# SCH_Aquacontrol_2026-05-27.net
KiCad netlist of a schematic drawn in EasyEDA
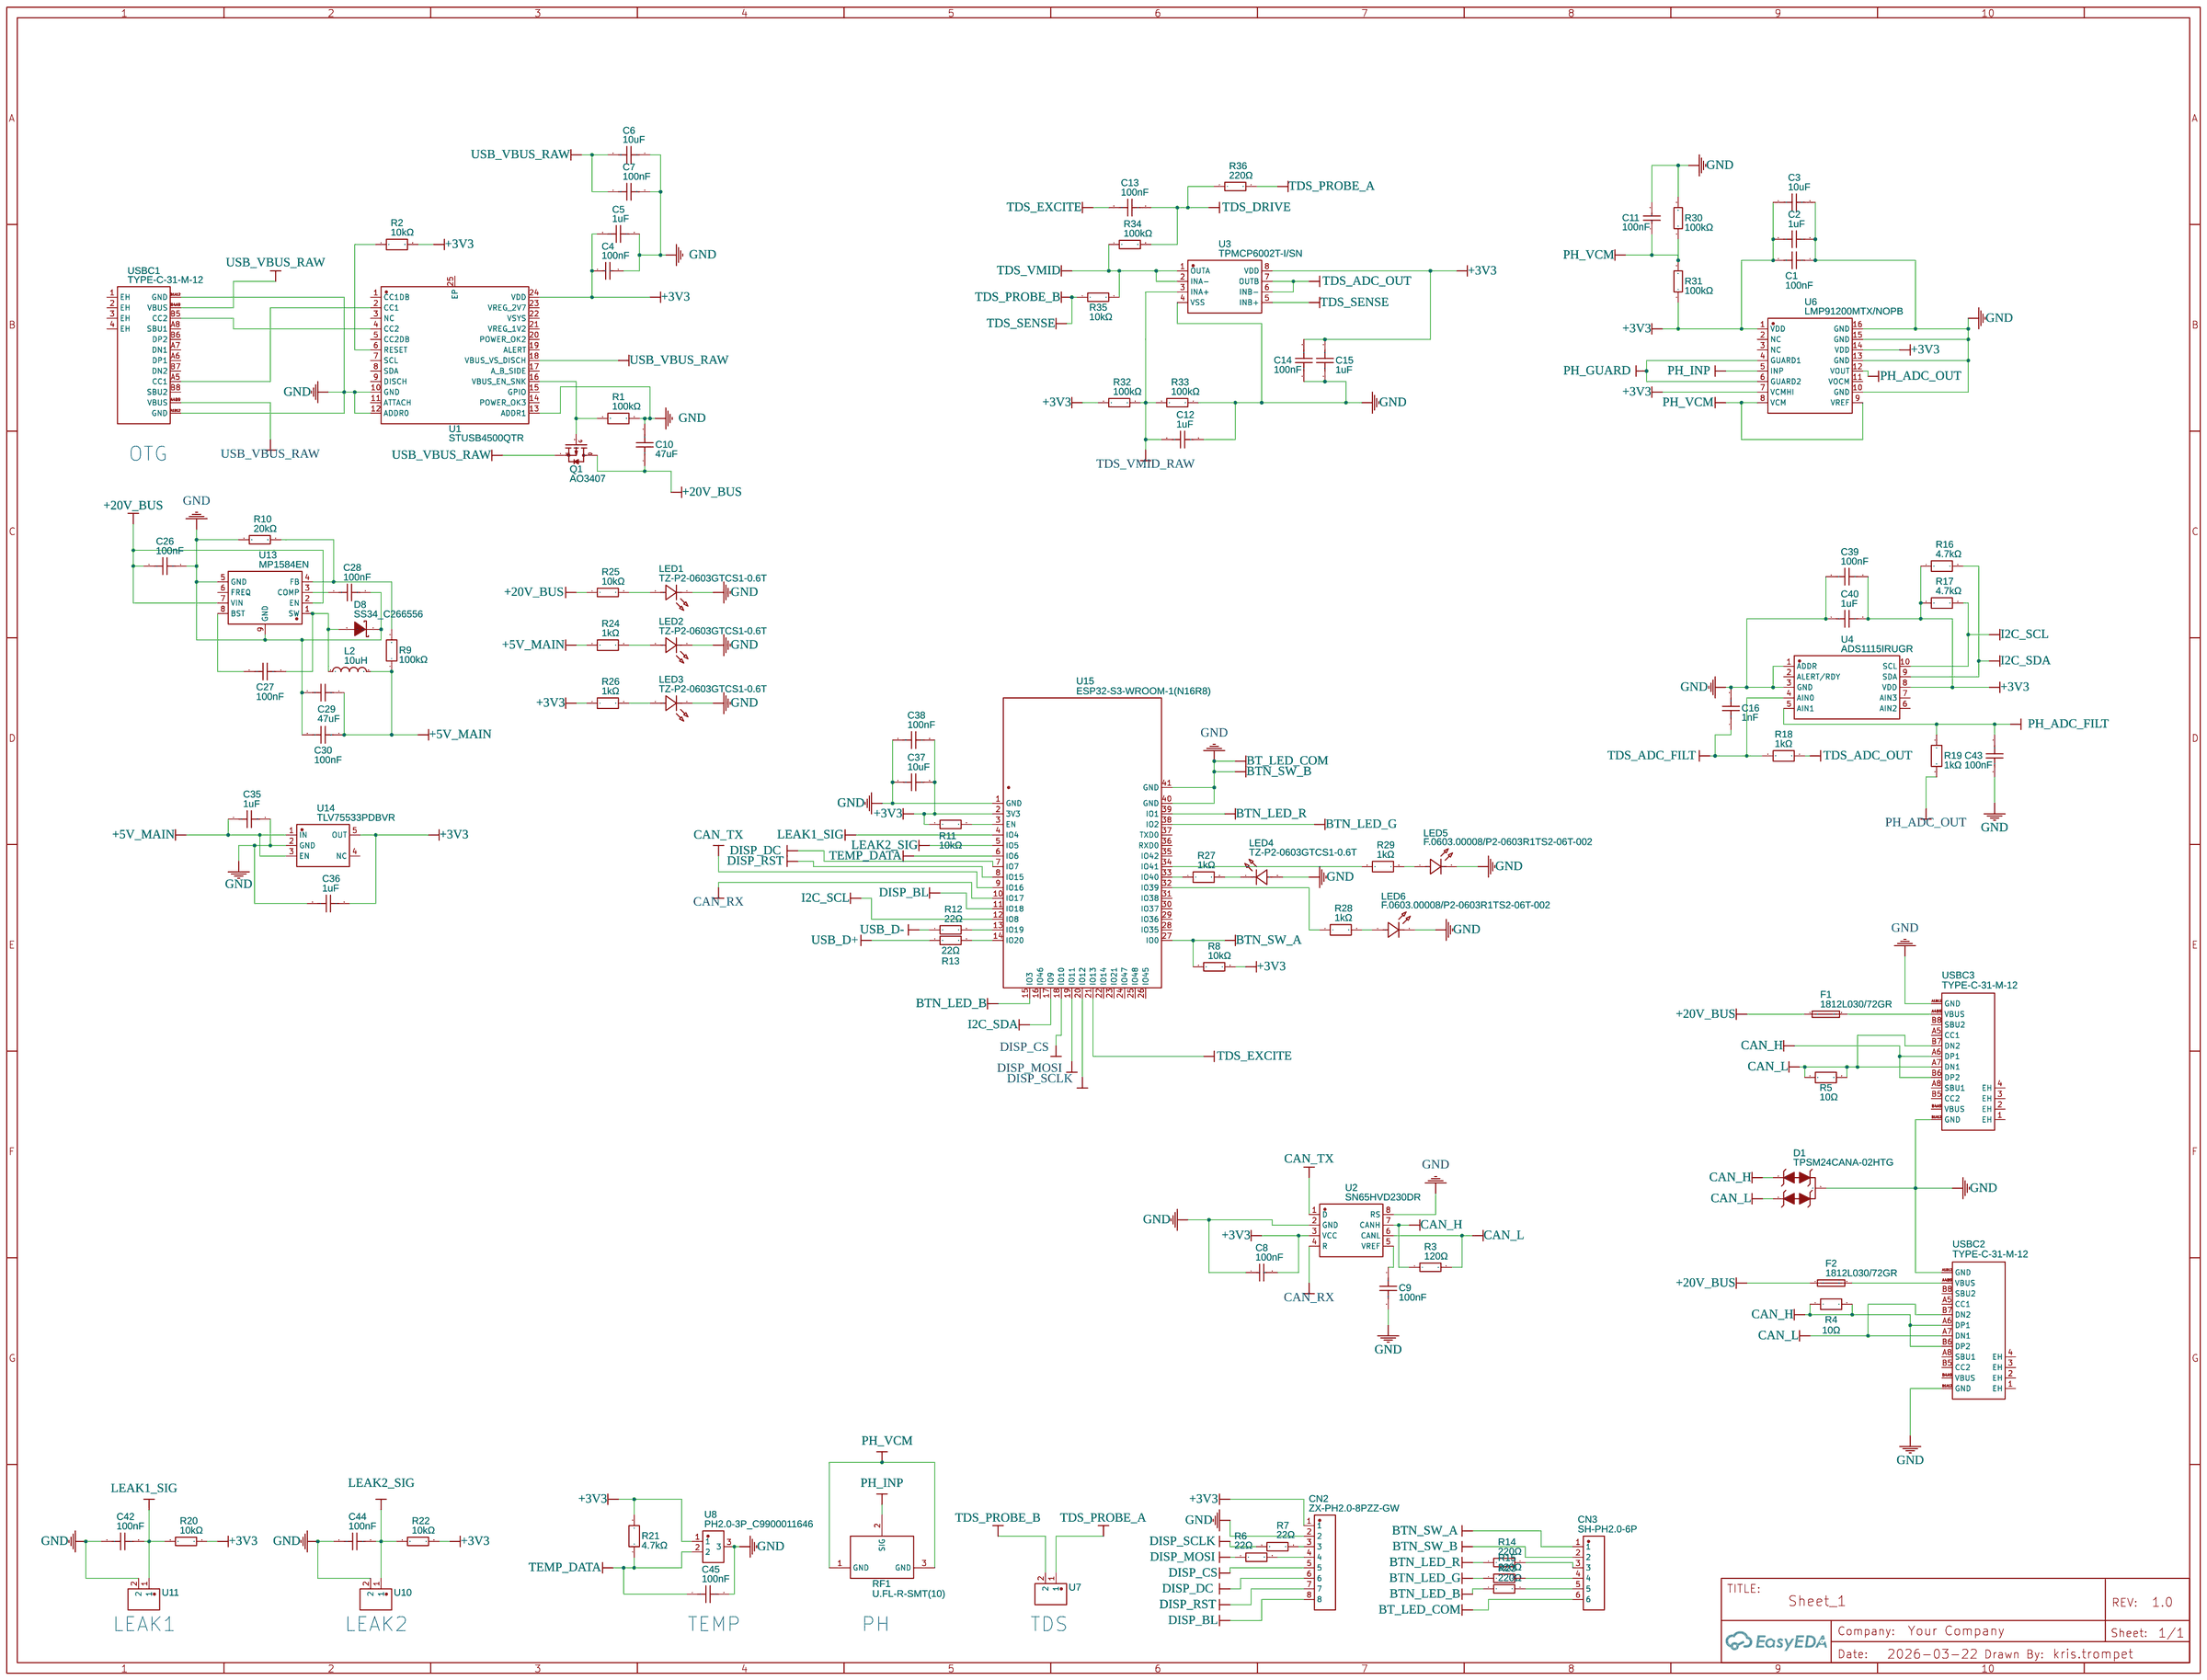
[diagram p0: schematic sheet]

(export (version "E")
  (design (tool "Eeschema 10.0.6"))
  (components
    (comp (ref "C1")
      (value "100nF")
      (fields (field (name "Manufacturer Part") "0603B104J250NT") (field (name "Manufacturer") "FH(风华)"))
      (libsource (lib "") (part "0603B104J250NT"))
    )
    (comp (ref "C2")
      (value "1uF")
      (fields
        (field (name "Manufacturer Part") "TCC0603X5R105M250CT")
        (field (name "Manufacturer") "CCTC(三环)")
      )
      (libsource (lib "") (part "TCC0603X5R105M250CT"))
    )
    (comp (ref "C3")
      (value "10uF")
      (fields
        (field (name "Manufacturer Part") "0805X5R106M500NT")
        (field (name "Manufacturer") "AIDE(爱迪电容)")
      )
      (libsource (lib "") (part "0805X5R106M500NT"))
    )
    (comp (ref "C4")
      (value "100nF")
      (fields (field (name "Manufacturer Part") "06035C104KAT2A") (field (name "Manufacturer") "Kyocera AVX"))
      (libsource (lib "") (part "06035C104KAT2A"))
    )
    (comp (ref "C5")
      (value "1uF")
      (fields (field (name "Manufacturer Part") "0603B105J160CT") (field (name "Manufacturer") "Walsin(华新科)"))
      (libsource (lib "") (part "0603B105J160CT"))
    )
    (comp (ref "C6")
      (value "10uF")
      (fields (field (name "Manufacturer Part") "1206B106K100NT") (field (name "Manufacturer") "FH(风华)"))
      (libsource (lib "") (part "1206B106K100NT"))
    )
    (comp (ref "C7")
      (value "100nF")
      (fields (field (name "Manufacturer Part") "0603B104J500NT") (field (name "Manufacturer") "FH(风华)"))
      (libsource (lib "") (part "0603B104J500NT"))
    )
    (comp (ref "C8")
      (value "100nF")
      (fields (field (name "Manufacturer Part") "06035C104KAT2A") (field (name "Manufacturer") "Kyocera AVX"))
      (libsource (lib "") (part "06035C104KAT2A"))
    )
    (comp (ref "C9")
      (value "100nF")
      (fields
        (field (name "Manufacturer Part") "0603X7R104K100NT")
        (field (name "Manufacturer") "AIDE(爱迪电容)")
      )
      (libsource (lib "") (part "0603X7R104K100NT_1"))
    )
    (comp (ref "C10")
      (value "47uF")
      (fields
        (field (name "Manufacturer Part") "TCC1206X5R476M100HT")
        (field (name "Manufacturer") "CCTC(三环)")
      )
      (libsource (lib "") (part "TCC1206X5R476M100HT"))
    )
    (comp (ref "C11")
      (value "100nF")
      (fields
        (field (name "Manufacturer Part") "CT41G-0603-2X1-50V-0.1uF-K(N)")
        (field (name "Manufacturer") "TORCH(火炬)")
      )
      (libsource (lib "") (part "CT41G-0603-2X1-50V-0.1μF-K(N)"))
    )
    (comp (ref "C12")
      (value "1uF")
      (fields
        (field (name "Manufacturer Part") "TCC0603X5R105M250CT")
        (field (name "Manufacturer") "CCTC(三环)")
      )
      (libsource (lib "") (part "TCC0603X5R105M250CT"))
    )
    (comp (ref "C13")
      (value "100nF")
      (fields
        (field (name "Manufacturer Part") "0603X7R104K100NT")
        (field (name "Manufacturer") "AIDE(爱迪电容)")
      )
      (libsource (lib "") (part "0603X7R104K100NT_3"))
    )
    (comp (ref "C14")
      (value "100nF")
      (fields
        (field (name "Manufacturer Part") "0603X7R104K100NT")
        (field (name "Manufacturer") "AIDE(爱迪电容)")
      )
      (libsource (lib "") (part "0603X7R104K100NT"))
    )
    (comp (ref "C15")
      (value "1uF")
      (fields
        (field (name "Manufacturer Part") "TCC0603X5R105M250CT")
        (field (name "Manufacturer") "CCTC(三环)")
      )
      (libsource (lib "") (part "TCC0603X5R105M250CT_1"))
    )
    (comp (ref "C16")
      (value "1nF")
      (fields
        (field (name "Manufacturer Part") "AC0603KRX7R9BB102")
        (field (name "Manufacturer") "YAGEO(国巨)")
      )
      (libsource (lib "") (part "AC0603KRX7R9BB102"))
    )
    (comp (ref "C26")
      (value "100nF")
      (fields (field (name "Manufacturer Part") "0603B104J250NT") (field (name "Manufacturer") "FH(风华)"))
      (libsource (lib "") (part "0603B104J250NT"))
    )
    (comp (ref "C27")
      (value "100nF")
      (fields (field (name "Manufacturer Part") "0603B104J250NT") (field (name "Manufacturer") "FH(风华)"))
      (libsource (lib "") (part "0603B104J250NT"))
    )
    (comp (ref "C28")
      (value "100nF")
      (fields (field (name "Manufacturer Part") "0603B104J250NT") (field (name "Manufacturer") "FH(风华)"))
      (libsource (lib "") (part "0603B104J250NT_1"))
    )
    (comp (ref "C29")
      (value "47uF")
      (fields
        (field (name "Manufacturer Part") "CGA0603X5R476M6R3JT")
        (field (name "Manufacturer") "HRE(芯声)")
      )
      (libsource (lib "") (part "CGA0603X5R476M6R3JT"))
    )
    (comp (ref "C30")
      (value "100nF")
      (fields (field (name "Manufacturer Part") "0603B104J250NT") (field (name "Manufacturer") "FH(风华)"))
      (libsource (lib "") (part "0603B104J250NT"))
    )
    (comp (ref "C35")
      (value "1uF")
      (fields
        (field (name "Manufacturer Part") "CSA0603X5R105K160JT")
        (field (name "Manufacturer") "HRE(芯声)")
      )
      (libsource (lib "") (part "CSA0603X5R105K160JT"))
    )
    (comp (ref "C36")
      (value "1uF")
      (fields
        (field (name "Manufacturer Part") "CSA0603X5R105K160JT")
        (field (name "Manufacturer") "HRE(芯声)")
      )
      (libsource (lib "") (part "CSA0603X5R105K160JT"))
    )
    (comp (ref "C37")
      (value "10uF")
      (fields
        (field (name "Manufacturer Part") "CGA0805X7R106K100MT")
        (field (name "Manufacturer") "HRE(芯声)")
      )
      (libsource (lib "") (part "CGA0805X7R106K100MT"))
    )
    (comp (ref "C38")
      (value "100nF")
      (fields
        (field (name "Manufacturer Part") "0603X7R104K100NT")
        (field (name "Manufacturer") "AIDE(爱迪电容)")
      )
      (libsource (lib "") (part "0603X7R104K100NT_2"))
    )
    (comp (ref "C39")
      (value "100nF")
      (fields
        (field (name "Manufacturer Part") "0603X7R104K100NT")
        (field (name "Manufacturer") "AIDE(爱迪电容)")
      )
      (libsource (lib "") (part "0603X7R104K100NT_2"))
    )
    (comp (ref "C40")
      (value "1uF")
      (fields
        (field (name "Manufacturer Part") "TCC0603X5R105M250CT")
        (field (name "Manufacturer") "CCTC(三环)")
      )
      (libsource (lib "") (part "TCC0603X5R105M250CT"))
    )
    (comp (ref "C42")
      (value "100nF")
      (fields
        (field (name "Manufacturer Part") "0603X7R104K100NT")
        (field (name "Manufacturer") "AIDE(爱迪电容)")
      )
      (libsource (lib "") (part "0603X7R104K100NT_2"))
    )
    (comp (ref "C43")
      (value "100nF")
      (fields
        (field (name "Manufacturer Part") "0603X7R104K100NT")
        (field (name "Manufacturer") "AIDE(爱迪电容)")
      )
      (libsource (lib "") (part "0603X7R104K100NT"))
    )
    (comp (ref "C44")
      (value "100nF")
      (fields
        (field (name "Manufacturer Part") "0603X7R104K100NT")
        (field (name "Manufacturer") "AIDE(爱迪电容)")
      )
      (libsource (lib "") (part "0603X7R104K100NT_2"))
    )
    (comp (ref "C45")
      (value "100nF")
      (fields
        (field (name "Manufacturer Part") "0603X7R104K100NT")
        (field (name "Manufacturer") "AIDE(爱迪电容)")
      )
      (libsource (lib "") (part "0603X7R104K100NT_2"))
    )
    (comp (ref "CN2")
      (value "ZX-PH2.0-8PZZ-GW")
      (fields (field (name "Manufacturer") "Megastar(兆星)"))
      (libsource (lib "") (part "ZX-PH2.0-8PZZ-GW"))
    )
    (comp (ref "CN3")
      (value "SH-PH2.0-6P")
      (fields (field (name "Manufacturer") "深海电子"))
      (libsource (lib "") (part "SH-PH2.0-6P"))
    )
    (comp (ref "D1")
      (value "TPSM24CANA-02HTG")
      (fields (field (name "Manufacturer") "TECH PUBLIC(台舟)"))
      (libsource (lib "") (part "TPSM24CANA-02HTG"))
    )
    (comp (ref "D8")
      (value "SS34_C266556")
      (fields (field (name "Manufacturer Part") "SS34") (field (name "Manufacturer") "BORN(伯恩半导体)"))
      (libsource (lib "") (part "SS34_C266556"))
    )
    (comp (ref "F1")
      (value "1812L030/72GR")
      (fields (field (name "Manufacturer") "LUTE(陆特)"))
      (libsource (lib "") (part "1812L030/72GR"))
    )
    (comp (ref "F2")
      (value "1812L030/72GR")
      (fields (field (name "Manufacturer") "LUTE(陆特)"))
      (libsource (lib "") (part "1812L030/72GR"))
    )
    (comp (ref "L2")
      (value "10uH")
      (fields (field (name "Manufacturer Part") "SMDRI129-100MT") (field (name "Manufacturer") "SXN(顺翔诺)"))
      (libsource (lib "") (part "SMDRI129-100MT"))
    )
    (comp (ref "LED1")
      (value "TZ-P2-0603GTCS1-0.6T")
      (fields (field (name "Manufacturer") "TUOZHAN(拓展光电)"))
      (libsource (lib "") (part "TZ-P2-0603GTCS1-0.6T_1"))
    )
    (comp (ref "LED2")
      (value "TZ-P2-0603GTCS1-0.6T")
      (fields (field (name "Manufacturer") "TUOZHAN(拓展光电)"))
      (libsource (lib "") (part "TZ-P2-0603GTCS1-0.6T_1"))
    )
    (comp (ref "LED3")
      (value "TZ-P2-0603GTCS1-0.6T")
      (fields (field (name "Manufacturer") "TUOZHAN(拓展光电)"))
      (libsource (lib "") (part "TZ-P2-0603GTCS1-0.6T_1"))
    )
    (comp (ref "LED4")
      (value "TZ-P2-0603GTCS1-0.6T")
      (fields (field (name "Manufacturer") "TUOZHAN(拓展光电)"))
      (libsource (lib "") (part "TZ-P2-0603GTCS1-0.6T"))
    )
    (comp (ref "LED5")
      (value "F.0603.00008/P2-0603R1TS2-06T-002")
      (fields (field (name "Manufacturer") "TUOZHAN(拓展光电)"))
      (libsource (lib "") (part "F.0603.00008/P2-0603R1TS2-06T-002"))
    )
    (comp (ref "LED6")
      (value "F.0603.00008/P2-0603R1TS2-06T-002")
      (fields (field (name "Manufacturer") "TUOZHAN(拓展光电)"))
      (libsource (lib "") (part "F.0603.00008/P2-0603R1TS2-06T-002"))
    )
    (comp (ref "Q1")
      (value "AO3407")
      (fields (field (name "Manufacturer") "Hottech(合科泰)"))
      (libsource (lib "") (part "AO3407"))
    )
    (comp (ref "R1")
      (value "100kΩ")
      (fields
        (field (name "Manufacturer Part") "0603WAD1003T5E")
        (field (name "Manufacturer") "UNI-ROYAL(厚声)")
      )
      (libsource (lib "") (part "0603WAD1003T5E"))
    )
    (comp (ref "R2")
      (value "10kΩ")
      (fields (field (name "Manufacturer Part") "AC0603DR-0710KL") (field (name "Manufacturer") "YAGEO(国巨)"))
      (libsource (lib "") (part "AC0603DR-0710KL"))
    )
    (comp (ref "R3")
      (value "120Ω")
      (fields
        (field (name "Manufacturer Part") "0603WAF1200T5E")
        (field (name "Manufacturer") "UNI-ROYAL(厚声)")
      )
      (libsource (lib "") (part "0603WAF1200T5E"))
    )
    (comp (ref "R4")
      (value "10Ω")
      (fields (field (name "Manufacturer Part") "FRC0603F10R0TS") (field (name "Manufacturer") "FOJAN(富捷)"))
      (libsource (lib "") (part "FRC0603F10R0TS"))
    )
    (comp (ref "R5")
      (value "10Ω")
      (fields (field (name "Manufacturer Part") "FRC0603F10R0TS") (field (name "Manufacturer") "FOJAN(富捷)"))
      (libsource (lib "") (part "FRC0603F10R0TS"))
    )
    (comp (ref "R6")
      (value "22Ω")
      (fields (field (name "Manufacturer Part") "RC0603FR-0722RL") (field (name "Manufacturer") "YAGEO(国巨)"))
      (libsource (lib "") (part "RC0603FR-0722RL"))
    )
    (comp (ref "R7")
      (value "22Ω")
      (fields (field (name "Manufacturer Part") "RC0603FR-0722RL") (field (name "Manufacturer") "YAGEO(国巨)"))
      (libsource (lib "") (part "RC0603FR-0722RL"))
    )
    (comp (ref "R8")
      (value "10kΩ")
      (fields (field (name "Manufacturer Part") "AT0603FRE0710KL") (field (name "Manufacturer") "YAGEO(国巨)"))
      (libsource (lib "") (part "AT0603FRE0710KL"))
    )
    (comp (ref "R9")
      (value "100kΩ")
      (fields (field (name "Manufacturer Part") "RC0603FR-07100KP") (field (name "Manufacturer") "YAGEO(国巨)"))
      (libsource (lib "") (part "RC0603FR-07100KP"))
    )
    (comp (ref "R10")
      (value "20kΩ")
      (fields (field (name "Manufacturer Part") "AF0603FR-0720KL") (field (name "Manufacturer") "YAGEO(国巨)"))
      (libsource (lib "") (part "AF0603FR-0720KL"))
    )
    (comp (ref "R11")
      (value "10kΩ")
      (fields (field (name "Manufacturer Part") "RT0603DRD0710KL") (field (name "Manufacturer") "YAGEO(国巨)"))
      (libsource (lib "") (part "RT0603DRD0710KL"))
    )
    (comp (ref "R12")
      (value "22Ω")
      (fields (field (name "Manufacturer Part") "RC0603FR-0722RL") (field (name "Manufacturer") "YAGEO(国巨)"))
      (libsource (lib "") (part "RC0603FR-0722RL"))
    )
    (comp (ref "R13")
      (value "22Ω")
      (fields (field (name "Manufacturer Part") "RC0603FR-0722RL") (field (name "Manufacturer") "YAGEO(国巨)"))
      (libsource (lib "") (part "RC0603FR-0722RL"))
    )
    (comp (ref "R14")
      (value "220Ω")
      (fields (field (name "Manufacturer Part") "AC0603FR-07220RL") (field (name "Manufacturer") "YAGEO(国巨)"))
      (libsource (lib "") (part "AC0603FR-07220RL"))
    )
    (comp (ref "R15")
      (value "220Ω")
      (fields (field (name "Manufacturer Part") "AC0603FR-07220RL") (field (name "Manufacturer") "YAGEO(国巨)"))
      (libsource (lib "") (part "AC0603FR-07220RL"))
    )
    (comp (ref "R16")
      (value "4.7kΩ")
      (fields
        (field (name "Manufacturer Part") "HoLTT0603-1/10W-4.7K-1%")
        (field (name "Manufacturer") "Milliohm(毫欧)")
      )
      (libsource (lib "") (part "HOLTT0603-1/10W-4.7K-1%"))
    )
    (comp (ref "R17")
      (value "4.7kΩ")
      (fields
        (field (name "Manufacturer Part") "HoLTT0603-1/10W-4.7K-1%")
        (field (name "Manufacturer") "Milliohm(毫欧)")
      )
      (libsource (lib "") (part "HOLTT0603-1/10W-4.7K-1%"))
    )
    (comp (ref "R18")
      (value "1kΩ")
      (fields
        (field (name "Manufacturer Part") "RMC 0603 1K J N")
        (field (name "Manufacturer") "Tyohm(幸亚电阻)")
      )
      (libsource (lib "") (part "RMC 0603 1K J N_2"))
    )
    (comp (ref "R19")
      (value "1kΩ")
      (fields
        (field (name "Manufacturer Part") "RMC 0603 1K J N")
        (field (name "Manufacturer") "Tyohm(幸亚电阻)")
      )
      (libsource (lib "") (part "RMC 0603 1K J N"))
    )
    (comp (ref "R20")
      (value "10kΩ")
      (fields (field (name "Manufacturer Part") "RT0603DRD0710KL") (field (name "Manufacturer") "YAGEO(国巨)"))
      (libsource (lib "") (part "RT0603DRD0710KL"))
    )
    (comp (ref "R21")
      (value "4.7kΩ")
      (fields
        (field (name "Manufacturer Part") "HoLTT0603-1/10W-4.7K-1%")
        (field (name "Manufacturer") "Milliohm(毫欧)")
      )
      (libsource (lib "") (part "HOLTT0603-1/10W-4.7K-1%_1"))
    )
    (comp (ref "R22")
      (value "10kΩ")
      (fields (field (name "Manufacturer Part") "RT0603DRD0710KL") (field (name "Manufacturer") "YAGEO(国巨)"))
      (libsource (lib "") (part "RT0603DRD0710KL"))
    )
    (comp (ref "R23")
      (value "220Ω")
      (fields (field (name "Manufacturer Part") "AC0603FR-07220RL") (field (name "Manufacturer") "YAGEO(国巨)"))
      (libsource (lib "") (part "AC0603FR-07220RL"))
    )
    (comp (ref "R24")
      (value "1kΩ")
      (fields
        (field (name "Manufacturer Part") "RMC 0603 1K J N")
        (field (name "Manufacturer") "Tyohm(幸亚电阻)")
      )
      (libsource (lib "") (part "RMC 0603 1K J N_1"))
    )
    (comp (ref "R25")
      (value "10kΩ")
      (fields (field (name "Manufacturer Part") "AT0603FRE0710KL") (field (name "Manufacturer") "YAGEO(国巨)"))
      (libsource (lib "") (part "AT0603FRE0710KL"))
    )
    (comp (ref "R26")
      (value "1kΩ")
      (fields
        (field (name "Manufacturer Part") "RMC 0603 1K J N")
        (field (name "Manufacturer") "Tyohm(幸亚电阻)")
      )
      (libsource (lib "") (part "RMC 0603 1K J N_1"))
    )
    (comp (ref "R27")
      (value "1kΩ")
      (fields
        (field (name "Manufacturer Part") "RMC 0603 1K J N")
        (field (name "Manufacturer") "Tyohm(幸亚电阻)")
      )
      (libsource (lib "") (part "RMC 0603 1K J N_1"))
    )
    (comp (ref "R28")
      (value "1kΩ")
      (fields
        (field (name "Manufacturer Part") "RMC 0603 1K J N")
        (field (name "Manufacturer") "Tyohm(幸亚电阻)")
      )
      (libsource (lib "") (part "RMC 0603 1K J N_1"))
    )
    (comp (ref "R29")
      (value "1kΩ")
      (fields
        (field (name "Manufacturer Part") "RMC 0603 1K J N")
        (field (name "Manufacturer") "Tyohm(幸亚电阻)")
      )
      (libsource (lib "") (part "RMC 0603 1K J N_1"))
    )
    (comp (ref "R30")
      (value "100kΩ")
      (fields (field (name "Manufacturer Part") "RT0603BRE07100KL") (field (name "Manufacturer") "YAGEO(国巨)"))
      (libsource (lib "") (part "RT0603BRE07100KL"))
    )
    (comp (ref "R31")
      (value "100kΩ")
      (fields (field (name "Manufacturer Part") "RT0603BRE07100KL") (field (name "Manufacturer") "YAGEO(国巨)"))
      (libsource (lib "") (part "RT0603BRE07100KL"))
    )
    (comp (ref "R32")
      (value "100kΩ")
      (fields (field (name "Manufacturer Part") "RT0603BRE07100KL") (field (name "Manufacturer") "YAGEO(国巨)"))
      (libsource (lib "") (part "RT0603BRE07100KL_1"))
    )
    (comp (ref "R33")
      (value "100kΩ")
      (fields (field (name "Manufacturer Part") "RT0603BRE07100KL") (field (name "Manufacturer") "YAGEO(国巨)"))
      (libsource (lib "") (part "RT0603BRE07100KL_1"))
    )
    (comp (ref "R34")
      (value "100kΩ")
      (fields (field (name "Manufacturer Part") "RT0603BRE07100KL") (field (name "Manufacturer") "YAGEO(国巨)"))
      (libsource (lib "") (part "RT0603BRE07100KL_1"))
    )
    (comp (ref "R35")
      (value "10kΩ")
      (fields (field (name "Manufacturer Part") "AT0603FRE0710KL") (field (name "Manufacturer") "YAGEO(国巨)"))
      (libsource (lib "") (part "AT0603FRE0710KL"))
    )
    (comp (ref "R36")
      (value "220Ω")
      (fields (field (name "Manufacturer Part") "AC0603FR-07220RL") (field (name "Manufacturer") "YAGEO(国巨)"))
      (libsource (lib "") (part "AC0603FR-07220RL"))
    )
    (comp (ref "RF1")
      (value "U.FL-R-SMT(10)")
      (fields (field (name "Manufacturer") "HRS(广濑)"))
      (libsource (lib "") (part "U.FL-R-SMT(10)"))
    )
    (comp (ref "U1")
      (value "STUSB4500QTR")
      (fields (field (name "Manufacturer") "ST(意法半导体)"))
      (libsource (lib "") (part "STUSB4500QTR"))
    )
    (comp (ref "U2")
      (value "SN65HVD230DR")
      (fields (field (name "Manufacturer") "TI(德州仪器)"))
      (libsource (lib "") (part "SN65HVD230DR"))
    )
    (comp (ref "U3")
      (value "TPMCP6002T-I/SN")
      (fields (field (name "Manufacturer") "TECH PUBLIC(台舟)"))
      (libsource (lib "") (part "TPMCP6002T-I/SN"))
    )
    (comp (ref "U4")
      (value "ADS1115IRUGR")
      (fields (field (name "Manufacturer") "TI(德州仪器)"))
      (libsource (lib "") (part "ADS1115IRUGR"))
    )
    (comp (ref "U6")
      (value "LMP91200MTX/NOPB")
      (fields (field (name "Manufacturer") "TI(德州仪器)"))
      (libsource (lib "") (part "LMP91200MTX/NOPB"))
    )
    (comp (ref "U7")
      (value "PH2.0-2P_C9900095162")
      (fields (field (name "Manufacturer Part") "PH2.0-2P"))
      (libsource (lib "") (part "PH2.0-2P_C9900095162"))
    )
    (comp (ref "U8")
      (value "PH2.0-3P_C9900011646")
      (fields (field (name "Manufacturer Part") "PH2.0-3P"))
      (libsource (lib "") (part "PH2.0-3P_C9900011646"))
    )
    (comp (ref "U10")
      (value "PH2.0-2P_C9900095162")
      (fields (field (name "Manufacturer Part") "PH2.0-2P"))
      (libsource (lib "") (part "PH2.0-2P_C9900095162"))
    )
    (comp (ref "U11")
      (value "PH2.0-2P_C9900095162")
      (fields (field (name "Manufacturer Part") "PH2.0-2P"))
      (libsource (lib "") (part "PH2.0-2P_C9900095162"))
    )
    (comp (ref "U13") (value "MP1584EN") (libsource (lib "") (part "MP1584EN")))
    (comp (ref "U14")
      (value "TLV75533PDBVR")
      (fields (field (name "Manufacturer") "TI(德州仪器)"))
      (libsource (lib "") (part "TLV75533PDBVR"))
    )
    (comp (ref "U15")
      (value "ESP32-S3-WROOM-1(N16R8)")
      (fields
        (field (name "Manufacturer Part") "ESP32-S3-WROOM-1-N16R8")
        (field (name "Manufacturer") "ESPRESSIF(乐鑫)")
      )
      (libsource (lib "") (part "ESP32-S3-WROOM-1(N16R8)"))
    )
    (comp (ref "USBC1")
      (value "TYPE-C-31-M-12")
      (fields (field (name "Manufacturer") "韩国韩荣"))
      (libsource (lib "") (part "TYPE-C-31-M-12"))
    )
    (comp (ref "USBC2")
      (value "TYPE-C-31-M-12")
      (fields (field (name "Manufacturer") "韩国韩荣"))
      (libsource (lib "") (part "TYPE-C-31-M-12_1"))
    )
    (comp (ref "USBC3")
      (value "TYPE-C-31-M-12")
      (fields (field (name "Manufacturer") "韩国韩荣"))
      (libsource (lib "") (part "TYPE-C-31-M-12_1"))
    )
  )
  (nets
    (net (code "1") (name "+3V3") (class "Default")
      (node (ref "C1") (pin "2") (pinfunction "2_2") (pintype "unspecified"))
      (node (ref "C14") (pin "2") (pinfunction "2_2") (pintype "unspecified"))
      (node (ref "C15") (pin "2") (pinfunction "2_2") (pintype "unspecified"))
      (node (ref "C2") (pin "1") (pinfunction "1_1") (pintype "unspecified"))
      (node (ref "C3") (pin "1") (pinfunction "1_1") (pintype "unspecified"))
      (node (ref "C36") (pin "2") (pinfunction "2_2") (pintype "unspecified"))
      (node (ref "C37") (pin "2") (pinfunction "2_2") (pintype "unspecified"))
      (node (ref "C38") (pin "2") (pinfunction "2_2") (pintype "unspecified"))
      (node (ref "C39") (pin "2") (pinfunction "2_2") (pintype "unspecified"))
      (node (ref "C4") (pin "1") (pinfunction "1_1") (pintype "input"))
      (node (ref "C40") (pin "2") (pinfunction "2_2") (pintype "unspecified"))
      (node (ref "C5") (pin "1") (pinfunction "1_1") (pintype "unspecified"))
      (node (ref "C8") (pin "2") (pinfunction "2_2") (pintype "input"))
      (node (ref "CN2") (pin "1") (pinfunction "1_1") (pintype "unspecified"))
      (node (ref "R11") (pin "1") (pinfunction "1_1") (pintype "unspecified"))
      (node (ref "R16") (pin "1") (pinfunction "1_1") (pintype "unspecified"))
      (node (ref "R17") (pin "1") (pinfunction "1_1") (pintype "unspecified"))
      (node (ref "R2") (pin "2") (pinfunction "2_2") (pintype "unspecified"))
      (node (ref "R20") (pin "2") (pinfunction "2_2") (pintype "unspecified"))
      (node (ref "R21") (pin "2") (pinfunction "2_2") (pintype "unspecified"))
      (node (ref "R22") (pin "2") (pinfunction "2_2") (pintype "unspecified"))
      (node (ref "R26") (pin "1") (pinfunction "1_1") (pintype "unspecified"))
      (node (ref "R31") (pin "1") (pinfunction "1_1") (pintype "unspecified"))
      (node (ref "R32") (pin "1") (pinfunction "1_1") (pintype "unspecified"))
      (node (ref "R8") (pin "2") (pinfunction "2_2") (pintype "input"))
      (node (ref "U1") (pin "24") (pinfunction "VDD_24") (pintype "unspecified"))
      (node (ref "U14") (pin "5") (pinfunction "OUT_5") (pintype "unspecified"))
      (node (ref "U15") (pin "2") (pinfunction "3V3_2") (pintype "unspecified"))
      (node (ref "U2") (pin "3") (pinfunction "VCC_3") (pintype "unspecified"))
      (node (ref "U3") (pin "8") (pinfunction "VDD_8") (pintype "unspecified"))
      (node (ref "U4") (pin "8") (pinfunction "VDD_8") (pintype "unspecified"))
      (node (ref "U6") (pin "1") (pinfunction "VDD_1") (pintype "unspecified"))
      (node (ref "U6") (pin "14") (pinfunction "VDD_14") (pintype "unspecified"))
      (node (ref "U6") (pin "7") (pinfunction "VCMHI_7") (pintype "unspecified"))
      (node (ref "U8") (pin "1") (pinfunction "1_1") (pintype "unspecified"))
    )
    (net (code "2") (name "+5V_MAIN") (class "Default")
      (node (ref "C29") (pin "1") (pinfunction "1_1") (pintype "unspecified"))
      (node (ref "C30") (pin "1") (pinfunction "1_1") (pintype "unspecified"))
      (node (ref "C35") (pin "1") (pinfunction "1_1") (pintype "unspecified"))
      (node (ref "L2") (pin "2") (pinfunction "2_2") (pintype "unspecified"))
      (node (ref "R24") (pin "1") (pinfunction "1_1") (pintype "unspecified"))
      (node (ref "R9") (pin "1") (pinfunction "1_1") (pintype "unspecified"))
      (node (ref "U14") (pin "1") (pinfunction "IN_1") (pintype "unspecified"))
      (node (ref "U14") (pin "3") (pinfunction "EN_3") (pintype "unspecified"))
    )
    (net (code "3") (name "+20V_BUS") (class "Default")
      (node (ref "C10") (pin "1") (pinfunction "1_1") (pintype "unspecified"))
      (node (ref "C26") (pin "2") (pinfunction "2_2") (pintype "unspecified"))
      (node (ref "F1") (pin "1") (pinfunction "1_1") (pintype "unspecified"))
      (node (ref "F2") (pin "1") (pinfunction "1_1") (pintype "unspecified"))
      (node (ref "Q1") (pin "3") (pinfunction "D_3") (pintype "unspecified"))
      (node (ref "R25") (pin "1") (pinfunction "1_1") (pintype "input"))
      (node (ref "U13") (pin "2") (pinfunction "EN_2") (pintype "unspecified"))
      (node (ref "U13") (pin "7") (pinfunction "VIN_7") (pintype "unspecified"))
    )
    (net (code "4") (name "BTN_LED_B") (class "Default")
      (node (ref "R23") (pin "1") (pinfunction "1_1") (pintype "input"))
      (node (ref "U15") (pin "15") (pinfunction "IO3_15") (pintype "unspecified"))
    )
    (net (code "5") (name "BTN_LED_G") (class "Default")
      (node (ref "R15") (pin "1") (pinfunction "1_1") (pintype "input"))
      (node (ref "U15") (pin "38") (pinfunction "IO2_38") (pintype "unspecified"))
    )
    (net (code "6") (name "BTN_LED_R") (class "Default")
      (node (ref "R14") (pin "1") (pinfunction "1_1") (pintype "input"))
      (node (ref "U15") (pin "39") (pinfunction "IO1_39") (pintype "unspecified"))
    )
    (net (code "7") (name "BTN_SW_A") (class "Default")
      (node (ref "CN3") (pin "1") (pinfunction "1_1") (pintype "unspecified"))
      (node (ref "R8") (pin "1") (pinfunction "1_1") (pintype "input"))
      (node (ref "U15") (pin "27") (pinfunction "IO0_27") (pintype "unspecified"))
    )
    (net (code "8") (name "BTN_SW_B") (class "Default")
      (node (ref "C1") (pin "1") (pinfunction "1_1") (pintype "unspecified"))
      (node (ref "C10") (pin "2") (pinfunction "2_2") (pintype "unspecified"))
      (node (ref "C11") (pin "2") (pinfunction "2_2") (pintype "input"))
      (node (ref "C12") (pin "2") (pinfunction "2_2") (pintype "unspecified"))
      (node (ref "C14") (pin "1") (pinfunction "1_1") (pintype "unspecified"))
      (node (ref "C15") (pin "1") (pinfunction "1_1") (pintype "unspecified"))
      (node (ref "C16") (pin "2") (pinfunction "2_2") (pintype "unspecified"))
      (node (ref "C2") (pin "2") (pinfunction "2_2") (pintype "unspecified"))
      (node (ref "C26") (pin "1") (pinfunction "1_1") (pintype "unspecified"))
      (node (ref "C28") (pin "2") (pinfunction "2_2") (pintype "unspecified"))
      (node (ref "C29") (pin "2") (pinfunction "2_2") (pintype "unspecified"))
      (node (ref "C3") (pin "2") (pinfunction "2_2") (pintype "unspecified"))
      (node (ref "C30") (pin "2") (pinfunction "2_2") (pintype "unspecified"))
      (node (ref "C35") (pin "2") (pinfunction "2_2") (pintype "unspecified"))
      (node (ref "C36") (pin "1") (pinfunction "1_1") (pintype "unspecified"))
      (node (ref "C37") (pin "1") (pinfunction "1_1") (pintype "unspecified"))
      (node (ref "C38") (pin "1") (pinfunction "1_1") (pintype "unspecified"))
      (node (ref "C39") (pin "1") (pinfunction "1_1") (pintype "unspecified"))
      (node (ref "C4") (pin "2") (pinfunction "2_2") (pintype "input"))
      (node (ref "C40") (pin "1") (pinfunction "1_1") (pintype "unspecified"))
      (node (ref "C42") (pin "1") (pinfunction "1_1") (pintype "unspecified"))
      (node (ref "C43") (pin "1") (pinfunction "1_1") (pintype "unspecified"))
      (node (ref "C44") (pin "1") (pinfunction "1_1") (pintype "unspecified"))
      (node (ref "C45") (pin "2") (pinfunction "2_2") (pintype "unspecified"))
      (node (ref "C5") (pin "2") (pinfunction "2_2") (pintype "unspecified"))
      (node (ref "C6") (pin "1") (pinfunction "1_1") (pintype "unspecified"))
      (node (ref "C7") (pin "2") (pinfunction "2_2") (pintype "unspecified"))
      (node (ref "C8") (pin "1") (pinfunction "1_1") (pintype "input"))
      (node (ref "C9") (pin "2") (pinfunction "2_2") (pintype "unspecified"))
      (node (ref "CN2") (pin "2") (pinfunction "2_2") (pintype "unspecified"))
      (node (ref "CN3") (pin "2") (pinfunction "2_2") (pintype "unspecified"))
      (node (ref "CN3") (pin "6") (pinfunction "6_6") (pintype "unspecified"))
      (node (ref "D1") (pin "3") (pinfunction "3_3") (pintype "unspecified"))
      (node (ref "D8") (pin "1") (pinfunction "C_1") (pintype "unspecified"))
      (node (ref "LED1") (pin "1") (pinfunction "-_1") (pintype "unspecified"))
      (node (ref "LED2") (pin "1") (pinfunction "-_1") (pintype "unspecified"))
      (node (ref "LED3") (pin "1") (pinfunction "-_1") (pintype "unspecified"))
      (node (ref "LED4") (pin "2") (pinfunction "+_2") (pintype "unspecified"))
      (node (ref "LED5") (pin "2") (pinfunction "-_2") (pintype "unspecified"))
      (node (ref "LED6") (pin "2") (pinfunction "-_2") (pintype "unspecified"))
      (node (ref "R1") (pin "2") (pinfunction "2_2") (pintype "unspecified"))
      (node (ref "R10") (pin "1") (pinfunction "1_1") (pintype "unspecified"))
      (node (ref "R30") (pin "2") (pinfunction "2_2") (pintype "unspecified"))
      (node (ref "R33") (pin "2") (pinfunction "2_2") (pintype "unspecified"))
      (node (ref "U1") (pin "10") (pinfunction "GND_10") (pintype "unspecified"))
      (node (ref "U1") (pin "12") (pinfunction "ADDR0_12") (pintype "unspecified"))
      (node (ref "U1") (pin "13") (pinfunction "ADDR1_13") (pintype "unspecified"))
      (node (ref "U10") (pin "2") (pinfunction "2_2") (pintype "unspecified"))
      (node (ref "U11") (pin "2") (pinfunction "2_2") (pintype "unspecified"))
      (node (ref "U13") (pin "5") (pinfunction "GND_5") (pintype "unspecified"))
      (node (ref "U13") (pin "9") (pinfunction "GND_9") (pintype "unspecified"))
      (node (ref "U14") (pin "2") (pinfunction "GND_2") (pintype "unspecified"))
      (node (ref "U15") (pin "1") (pinfunction "GND_1") (pintype "unspecified"))
      (node (ref "U15") (pin "40") (pinfunction "GND_40") (pintype "unspecified"))
      (node (ref "U15") (pin "41") (pinfunction "GND_41") (pintype "unspecified"))
      (node (ref "U2") (pin "2") (pinfunction "GND_2") (pintype "unspecified"))
      (node (ref "U2") (pin "8") (pinfunction "RS_8") (pintype "unspecified"))
      (node (ref "U3") (pin "4") (pinfunction "VSS_4") (pintype "unspecified"))
      (node (ref "U4") (pin "1") (pinfunction "ADDR_1") (pintype "unspecified"))
      (node (ref "U4") (pin "3") (pinfunction "GND_3") (pintype "unspecified"))
      (node (ref "U6") (pin "10") (pinfunction "GND_10") (pintype "unspecified"))
      (node (ref "U6") (pin "13") (pinfunction "GND_13") (pintype "unspecified"))
      (node (ref "U6") (pin "15") (pinfunction "GND_15") (pintype "unspecified"))
      (node (ref "U6") (pin "16") (pinfunction "GND_16") (pintype "unspecified"))
      (node (ref "U8") (pin "3") (pinfunction "3_3") (pintype "unspecified"))
      (node (ref "USBC1") (pin "A1B12") (pinfunction "GND_A1B12") (pintype "unspecified"))
      (node (ref "USBC1") (pin "B1A12") (pinfunction "GND_B1A12") (pintype "unspecified"))
      (node (ref "USBC2") (pin "A1B12") (pinfunction "GND_A1B12") (pintype "unspecified"))
      (node (ref "USBC2") (pin "B1A12") (pinfunction "GND_B1A12") (pintype "unspecified"))
      (node (ref "USBC3") (pin "A1B12") (pinfunction "GND_A1B12") (pintype "unspecified"))
      (node (ref "USBC3") (pin "B1A12") (pinfunction "GND_B1A12") (pintype "unspecified"))
    )
    (net (code "9") (name "CAN_H") (class "Default")
      (node (ref "D1") (pin "1") (pinfunction "1_1") (pintype "unspecified"))
      (node (ref "R3") (pin "1") (pinfunction "1_1") (pintype "input"))
      (node (ref "R4") (pin "1") (pinfunction "1_1") (pintype "unspecified"))
      (node (ref "R4") (pin "2") (pinfunction "2_2") (pintype "unspecified"))
      (node (ref "U2") (pin "7") (pinfunction "CANH_7") (pintype "unspecified"))
      (node (ref "USBC2") (pin "A6") (pinfunction "DP1_A6") (pintype "unspecified"))
      (node (ref "USBC2") (pin "B6") (pinfunction "DP2_B6") (pintype "unspecified"))
      (node (ref "USBC3") (pin "A6") (pinfunction "DP1_A6") (pintype "unspecified"))
      (node (ref "USBC3") (pin "B6") (pinfunction "DP2_B6") (pintype "unspecified"))
    )
    (net (code "10") (name "CAN_L") (class "Default")
      (node (ref "D1") (pin "2") (pinfunction "2_2") (pintype "unspecified"))
      (node (ref "R3") (pin "2") (pinfunction "2_2") (pintype "input"))
      (node (ref "R5") (pin "1") (pinfunction "1_1") (pintype "unspecified"))
      (node (ref "R5") (pin "2") (pinfunction "2_2") (pintype "unspecified"))
      (node (ref "U2") (pin "6") (pinfunction "CANL_6") (pintype "unspecified"))
      (node (ref "USBC2") (pin "A7") (pinfunction "DN1_A7") (pintype "unspecified"))
      (node (ref "USBC2") (pin "B7") (pinfunction "DN2_B7") (pintype "unspecified"))
      (node (ref "USBC3") (pin "A7") (pinfunction "DN1_A7") (pintype "unspecified"))
      (node (ref "USBC3") (pin "B7") (pinfunction "DN2_B7") (pintype "unspecified"))
    )
    (net (code "11") (name "CAN_RX") (class "Default")
      (node (ref "U15") (pin "10") (pinfunction "IO17_10") (pintype "unspecified"))
      (node (ref "U2") (pin "4") (pinfunction "R_4") (pintype "unspecified"))
    )
    (net (code "12") (name "CAN_TX") (class "Default")
      (node (ref "U15") (pin "9") (pinfunction "IO16_9") (pintype "unspecified"))
      (node (ref "U2") (pin "1") (pinfunction "D_1") (pintype "unspecified"))
    )
    (net (code "13") (name "DISP_BL") (class "Default")
      (node (ref "CN2") (pin "8") (pinfunction "8_8") (pintype "unspecified"))
      (node (ref "U15") (pin "11") (pinfunction "IO18_11") (pintype "unspecified"))
    )
    (net (code "14") (name "DISP_CS") (class "Default")
      (node (ref "CN2") (pin "5") (pinfunction "5_5") (pintype "unspecified"))
      (node (ref "U15") (pin "18") (pinfunction "IO10_18") (pintype "unspecified"))
    )
    (net (code "15") (name "DISP_DC") (class "Default")
      (node (ref "CN2") (pin "6") (pinfunction "6_6") (pintype "unspecified"))
      (node (ref "U15") (pin "7") (pinfunction "IO7_7") (pintype "unspecified"))
    )
    (net (code "16") (name "DISP_MOSI") (class "Default")
      (node (ref "R6") (pin "1") (pinfunction "1_1") (pintype "input"))
      (node (ref "U15") (pin "19") (pinfunction "IO11_19") (pintype "unspecified"))
    )
    (net (code "17") (name "DISP_RST") (class "Default")
      (node (ref "CN2") (pin "7") (pinfunction "7_7") (pintype "unspecified"))
      (node (ref "U15") (pin "8") (pinfunction "IO15_8") (pintype "unspecified"))
    )
    (net (code "18") (name "DISP_SCLK") (class "Default")
      (node (ref "R7") (pin "1") (pinfunction "1_1") (pintype "input"))
      (node (ref "U15") (pin "20") (pinfunction "IO12_20") (pintype "unspecified"))
    )
    (net (code "19") (name "I2C_SCL") (class "Default")
      (node (ref "R17") (pin "2") (pinfunction "2_2") (pintype "unspecified"))
      (node (ref "U15") (pin "12") (pinfunction "IO8_12") (pintype "unspecified"))
      (node (ref "U4") (pin "10") (pinfunction "SCL_10") (pintype "unspecified"))
    )
    (net (code "20") (name "I2C_SDA") (class "Default")
      (node (ref "R16") (pin "2") (pinfunction "2_2") (pintype "unspecified"))
      (node (ref "U15") (pin "17") (pinfunction "IO9_17") (pintype "unspecified"))
      (node (ref "U4") (pin "9") (pinfunction "SDA_9") (pintype "unspecified"))
    )
    (net (code "21") (name "LEAK1_SIG") (class "Default")
      (node (ref "C42") (pin "2") (pinfunction "2_2") (pintype "unspecified"))
      (node (ref "R20") (pin "1") (pinfunction "1_1") (pintype "unspecified"))
      (node (ref "U11") (pin "1") (pinfunction "1_1") (pintype "unspecified"))
      (node (ref "U15") (pin "4") (pinfunction "IO4_4") (pintype "unspecified"))
    )
    (net (code "22") (name "LEAK2_SIG") (class "Default")
      (node (ref "C44") (pin "2") (pinfunction "2_2") (pintype "unspecified"))
      (node (ref "R22") (pin "1") (pinfunction "1_1") (pintype "unspecified"))
      (node (ref "U10") (pin "1") (pinfunction "1_1") (pintype "unspecified"))
      (node (ref "U15") (pin "5") (pinfunction "IO5_5") (pintype "unspecified"))
    )
    (net (code "23") (name "Net-(CN2-Pad3)") (class "Default")
      (node (ref "CN2") (pin "3") (pinfunction "3_3") (pintype "unspecified"))
      (node (ref "R7") (pin "2") (pinfunction "2_2") (pintype "input"))
    )
    (net (code "24") (name "Net-(CN2-Pad4)") (class "Default")
      (node (ref "CN2") (pin "4") (pinfunction "4_4") (pintype "unspecified"))
      (node (ref "R6") (pin "2") (pinfunction "2_2") (pintype "input"))
    )
    (net (code "25") (name "Net-(CN3-Pad3)") (class "Default")
      (node (ref "CN3") (pin "3") (pinfunction "3_3") (pintype "unspecified"))
      (node (ref "R14") (pin "2") (pinfunction "2_2") (pintype "input"))
    )
    (net (code "26") (name "Net-(CN3-Pad4)") (class "Default")
      (node (ref "CN3") (pin "4") (pinfunction "4_4") (pintype "unspecified"))
      (node (ref "R15") (pin "2") (pinfunction "2_2") (pintype "input"))
    )
    (net (code "27") (name "Net-(CN3-Pad5)") (class "Default")
      (node (ref "CN3") (pin "5") (pinfunction "5_5") (pintype "unspecified"))
      (node (ref "R23") (pin "2") (pinfunction "2_2") (pintype "input"))
    )
    (net (code "28") (name "Net-(D8-A)") (class "Default")
      (node (ref "C27") (pin "1") (pinfunction "1_1") (pintype "unspecified"))
      (node (ref "D8") (pin "2") (pinfunction "A_2") (pintype "unspecified"))
      (node (ref "L2") (pin "1") (pinfunction "1_1") (pintype "unspecified"))
      (node (ref "U13") (pin "1") (pinfunction "SW_1") (pintype "unspecified"))
    )
    (net (code "29") (name "Net-(F1-Pad2)") (class "Default")
      (node (ref "F1") (pin "2") (pinfunction "2_2") (pintype "unspecified"))
      (node (ref "USBC3") (pin "A4B9") (pinfunction "VBUS_A4B9") (pintype "unspecified"))
    )
    (net (code "30") (name "Net-(F2-Pad2)") (class "Default")
      (node (ref "F2") (pin "2") (pinfunction "2_2") (pintype "unspecified"))
      (node (ref "USBC2") (pin "A4B9") (pinfunction "VBUS_A4B9") (pintype "unspecified"))
    )
    (net (code "31") (name "Net-(LED1-+)") (class "Default")
      (node (ref "LED1") (pin "2") (pinfunction "+_2") (pintype "unspecified"))
      (node (ref "R25") (pin "2") (pinfunction "2_2") (pintype "input"))
    )
    (net (code "32") (name "Net-(LED2-+)") (class "Default")
      (node (ref "LED2") (pin "2") (pinfunction "+_2") (pintype "unspecified"))
      (node (ref "R24") (pin "2") (pinfunction "2_2") (pintype "unspecified"))
    )
    (net (code "33") (name "Net-(LED3-+)") (class "Default")
      (node (ref "LED3") (pin "2") (pinfunction "+_2") (pintype "unspecified"))
      (node (ref "R26") (pin "2") (pinfunction "2_2") (pintype "unspecified"))
    )
    (net (code "34") (name "Net-(LED4--)") (class "Default")
      (node (ref "LED4") (pin "1") (pinfunction "-_1") (pintype "unspecified"))
      (node (ref "R27") (pin "2") (pinfunction "2_2") (pintype "unspecified"))
    )
    (net (code "35") (name "Net-(LED5-+)") (class "Default")
      (node (ref "LED5") (pin "1") (pinfunction "+_1") (pintype "unspecified"))
      (node (ref "R29") (pin "2") (pinfunction "2_2") (pintype "unspecified"))
    )
    (net (code "36") (name "Net-(LED6-+)") (class "Default")
      (node (ref "LED6") (pin "1") (pinfunction "+_1") (pintype "unspecified"))
      (node (ref "R28") (pin "2") (pinfunction "2_2") (pintype "unspecified"))
    )
    (net (code "37") (name "Net-(Q1-G)") (class "Default")
      (node (ref "Q1") (pin "1") (pinfunction "G_1") (pintype "unspecified"))
      (node (ref "R1") (pin "1") (pinfunction "1_1") (pintype "unspecified"))
      (node (ref "U1") (pin "16") (pinfunction "VBUS_EN_SNK_16") (pintype "unspecified"))
    )
    (net (code "38") (name "Net-(U1-CC1)") (class "Default")
      (node (ref "U1") (pin "2") (pinfunction "CC1_2") (pintype "unspecified"))
      (node (ref "USBC1") (pin "A5") (pinfunction "CC1_A5") (pintype "unspecified"))
    )
    (net (code "39") (name "Net-(U1-CC2)") (class "Default")
      (node (ref "U1") (pin "4") (pinfunction "CC2_4") (pintype "unspecified"))
      (node (ref "USBC1") (pin "B5") (pinfunction "CC2_B5") (pintype "unspecified"))
    )
    (net (code "40") (name "Net-(U1-RESET)") (class "Default")
      (node (ref "R2") (pin "1") (pinfunction "1_1") (pintype "unspecified"))
      (node (ref "U1") (pin "6") (pinfunction "RESET_6") (pintype "unspecified"))
    )
    (net (code "41") (name "Net-(U2-VREF)") (class "Default")
      (node (ref "C9") (pin "1") (pinfunction "1_1") (pintype "unspecified"))
      (node (ref "U2") (pin "5") (pinfunction "VREF_5") (pintype "unspecified"))
    )
    (net (code "42") (name "Net-(U13-BST)") (class "Default")
      (node (ref "C27") (pin "2") (pinfunction "2_2") (pintype "unspecified"))
      (node (ref "U13") (pin "8") (pinfunction "BST_8") (pintype "unspecified"))
    )
    (net (code "43") (name "Net-(U13-COMP)") (class "Default")
      (node (ref "C28") (pin "1") (pinfunction "1_1") (pintype "unspecified"))
      (node (ref "U13") (pin "3") (pinfunction "COMP_3") (pintype "unspecified"))
    )
    (net (code "44") (name "Net-(U13-FB)") (class "Default")
      (node (ref "R10") (pin "2") (pinfunction "2_2") (pintype "unspecified"))
      (node (ref "R9") (pin "2") (pinfunction "2_2") (pintype "unspecified"))
      (node (ref "U13") (pin "4") (pinfunction "FB_4") (pintype "unspecified"))
    )
    (net (code "45") (name "Net-(U15-EN)") (class "Default")
      (node (ref "R11") (pin "2") (pinfunction "2_2") (pintype "unspecified"))
      (node (ref "U15") (pin "3") (pinfunction "EN_3") (pintype "unspecified"))
    )
    (net (code "46") (name "Net-(U15-IO19)") (class "Default")
      (node (ref "R12") (pin "2") (pinfunction "2_2") (pintype "input"))
      (node (ref "U15") (pin "13") (pinfunction "IO19_13") (pintype "unspecified"))
    )
    (net (code "47") (name "Net-(U15-IO20)") (class "Default")
      (node (ref "R13") (pin "2") (pinfunction "2_2") (pintype "input"))
      (node (ref "U15") (pin "14") (pinfunction "IO20_14") (pintype "unspecified"))
    )
    (net (code "48") (name "Net-(U15-IO39)") (class "Default")
      (node (ref "R28") (pin "1") (pinfunction "1_1") (pintype "unspecified"))
      (node (ref "U15") (pin "32") (pinfunction "IO39_32") (pintype "unspecified"))
    )
    (net (code "49") (name "Net-(U15-IO40)") (class "Default")
      (node (ref "R27") (pin "1") (pinfunction "1_1") (pintype "unspecified"))
      (node (ref "U15") (pin "33") (pinfunction "IO40_33") (pintype "unspecified"))
    )
    (net (code "50") (name "Net-(U15-IO41)") (class "Default")
      (node (ref "R29") (pin "1") (pinfunction "1_1") (pintype "unspecified"))
      (node (ref "U15") (pin "34") (pinfunction "IO41_34") (pintype "unspecified"))
    )
    (net (code "51") (name "PH_ADC_FILT") (class "Default")
      (node (ref "C43") (pin "2") (pinfunction "2_2") (pintype "unspecified"))
      (node (ref "R19") (pin "1") (pinfunction "1_1") (pintype "unspecified"))
      (node (ref "U4") (pin "5") (pinfunction "AIN1_5") (pintype "unspecified"))
    )
    (net (code "52") (name "PH_ADC_OUT") (class "Default")
      (node (ref "R19") (pin "2") (pinfunction "2_2") (pintype "unspecified"))
      (node (ref "U6") (pin "12") (pinfunction "VOUT_12") (pintype "unspecified"))
    )
    (net (code "53") (name "PH_GUARD") (class "Default")
      (node (ref "U6") (pin "4") (pinfunction "GUARD1_4") (pintype "unspecified"))
      (node (ref "U6") (pin "6") (pinfunction "GUARD2_6") (pintype "unspecified"))
    )
    (net (code "54") (name "PH_INP") (class "Default")
      (node (ref "RF1") (pin "2") (pinfunction "SIG_2") (pintype "unspecified"))
      (node (ref "U6") (pin "5") (pinfunction "INP_5") (pintype "unspecified"))
    )
    (net (code "55") (name "PH_VCM") (class "Default")
      (node (ref "C11") (pin "1") (pinfunction "1_1") (pintype "input"))
      (node (ref "R30") (pin "1") (pinfunction "1_1") (pintype "unspecified"))
      (node (ref "R31") (pin "2") (pinfunction "2_2") (pintype "unspecified"))
      (node (ref "RF1") (pin "1") (pinfunction "GND_1") (pintype "unspecified"))
      (node (ref "RF1") (pin "3") (pinfunction "GND_3") (pintype "unspecified"))
      (node (ref "U6") (pin "8") (pinfunction "VCM_8") (pintype "unspecified"))
      (node (ref "U6") (pin "9") (pinfunction "VREF_9") (pintype "unspecified"))
    )
    (net (code "56") (name "TDS_ADC_FILT") (class "Default")
      (node (ref "C16") (pin "1") (pinfunction "1_1") (pintype "unspecified"))
      (node (ref "R18") (pin "2") (pinfunction "2_2") (pintype "unspecified"))
      (node (ref "U4") (pin "4") (pinfunction "AIN0_4") (pintype "unspecified"))
    )
    (net (code "57") (name "TDS_ADC_OUT") (class "Default")
      (node (ref "R18") (pin "1") (pinfunction "1_1") (pintype "unspecified"))
      (node (ref "U3") (pin "6") (pinfunction "INB-_6") (pintype "unspecified"))
      (node (ref "U3") (pin "7") (pinfunction "OUTB_7") (pintype "unspecified"))
    )
    (net (code "58") (name "TDS_DRIVE") (class "Default")
      (node (ref "C13") (pin "1") (pinfunction "1_1") (pintype "unspecified"))
      (node (ref "R34") (pin "2") (pinfunction "2_2") (pintype "unspecified"))
      (node (ref "R36") (pin "1") (pinfunction "1_1") (pintype "input"))
    )
    (net (code "59") (name "TDS_EXCITE") (class "Default")
      (node (ref "C13") (pin "2") (pinfunction "2_2") (pintype "unspecified"))
      (node (ref "U15") (pin "21") (pinfunction "IO13_21") (pintype "unspecified"))
    )
    (net (code "60") (name "TDS_PROBE_A") (class "Default")
      (node (ref "R36") (pin "2") (pinfunction "2_2") (pintype "input"))
      (node (ref "U7") (pin "1") (pinfunction "1_1") (pintype "unspecified"))
    )
    (net (code "61") (name "TDS_PROBE_B") (class "Default")
      (node (ref "R35") (pin "1") (pinfunction "1_1") (pintype "input"))
      (node (ref "U3") (pin "5") (pinfunction "INB+_5") (pintype "unspecified"))
      (node (ref "U7") (pin "2") (pinfunction "2_2") (pintype "unspecified"))
    )
    (net (code "62") (name "TDS_VMID") (class "Default")
      (node (ref "R34") (pin "1") (pinfunction "1_1") (pintype "unspecified"))
      (node (ref "R35") (pin "2") (pinfunction "2_2") (pintype "input"))
      (node (ref "U3") (pin "1") (pinfunction "OUTA_1") (pintype "unspecified"))
      (node (ref "U3") (pin "2") (pinfunction "INA-_2") (pintype "unspecified"))
    )
    (net (code "63") (name "TDS_VMID_RAW") (class "Default")
      (node (ref "C12") (pin "1") (pinfunction "1_1") (pintype "unspecified"))
      (node (ref "R32") (pin "2") (pinfunction "2_2") (pintype "unspecified"))
      (node (ref "R33") (pin "1") (pinfunction "1_1") (pintype "unspecified"))
      (node (ref "U3") (pin "3") (pinfunction "INA+_3") (pintype "unspecified"))
    )
    (net (code "64") (name "TEMP_DATA") (class "Default")
      (node (ref "C45") (pin "1") (pinfunction "1_1") (pintype "unspecified"))
      (node (ref "R21") (pin "1") (pinfunction "1_1") (pintype "unspecified"))
      (node (ref "U15") (pin "6") (pinfunction "IO6_6") (pintype "unspecified"))
      (node (ref "U8") (pin "2") (pinfunction "2_2") (pintype "unspecified"))
    )
    (net (code "65") (name "USB_D+") (class "Default")
      (node (ref "R13") (pin "1") (pinfunction "1_1") (pintype "input"))
    )
    (net (code "66") (name "USB_D-") (class "Default")
      (node (ref "R12") (pin "1") (pinfunction "1_1") (pintype "input"))
    )
    (net (code "67") (name "USB_VBUS_RAW") (class "Default")
      (node (ref "C6") (pin "2") (pinfunction "2_2") (pintype "unspecified"))
      (node (ref "C7") (pin "1") (pinfunction "1_1") (pintype "unspecified"))
      (node (ref "Q1") (pin "2") (pinfunction "S_2") (pintype "unspecified"))
      (node (ref "U1") (pin "18") (pinfunction "VBUS_VS_DISCH_18") (pintype "unspecified"))
      (node (ref "USBC1") (pin "A4B9") (pinfunction "VBUS_A4B9") (pintype "unspecified"))
      (node (ref "USBC1") (pin "B4A9") (pinfunction "VBUS_B4A9") (pintype "unspecified"))
    )
    (net (code "68") (name "unconnected-(U1-ALERT-Pad19)") (class "Default")
      (node (ref "U1") (pin "19") (pinfunction "ALERT_19") (pintype "unspecified"))
    )
    (net (code "69") (name "unconnected-(U1-ATTACH-Pad11)") (class "Default")
      (node (ref "U1") (pin "11") (pinfunction "ATTACH_11") (pintype "unspecified"))
    )
    (net (code "70") (name "unconnected-(U1-A_B_SIDE-Pad17)") (class "Default")
      (node (ref "U1") (pin "17") (pinfunction "A_B_SIDE_17") (pintype "unspecified"))
    )
    (net (code "71") (name "unconnected-(U1-CC1DB-Pad1)") (class "Default")
      (node (ref "U1") (pin "1") (pinfunction "CC1DB_1") (pintype "unspecified"))
    )
    (net (code "72") (name "unconnected-(U1-CC2DB-Pad5)") (class "Default")
      (node (ref "U1") (pin "5") (pinfunction "CC2DB_5") (pintype "unspecified"))
    )
    (net (code "73") (name "unconnected-(U1-DISCH-Pad9)") (class "Default")
      (node (ref "U1") (pin "9") (pinfunction "DISCH_9") (pintype "unspecified"))
    )
    (net (code "74") (name "unconnected-(U1-EP-Pad25)") (class "Default")
      (node (ref "U1") (pin "25") (pinfunction "EP_25") (pintype "unspecified"))
    )
    (net (code "75") (name "unconnected-(U1-GPIO-Pad15)") (class "Default")
      (node (ref "U1") (pin "15") (pinfunction "GPIO_15") (pintype "unspecified"))
    )
    (net (code "76") (name "unconnected-(U1-NC-Pad3)") (class "Default")
      (node (ref "U1") (pin "3") (pinfunction "NC_3") (pintype "unspecified"))
    )
    (net (code "77") (name "unconnected-(U1-POWER_OK2-Pad20)") (class "Default")
      (node (ref "U1") (pin "20") (pinfunction "POWER_OK2_20") (pintype "unspecified"))
    )
    (net (code "78") (name "unconnected-(U1-POWER_OK3-Pad14)") (class "Default")
      (node (ref "U1") (pin "14") (pinfunction "POWER_OK3_14") (pintype "unspecified"))
    )
    (net (code "79") (name "unconnected-(U1-SCL-Pad7)") (class "Default")
      (node (ref "U1") (pin "7") (pinfunction "SCL_7") (pintype "unspecified"))
    )
    (net (code "80") (name "unconnected-(U1-SDA-Pad8)") (class "Default")
      (node (ref "U1") (pin "8") (pinfunction "SDA_8") (pintype "unspecified"))
    )
    (net (code "81") (name "unconnected-(U1-VREG_1V2-Pad21)") (class "Default")
      (node (ref "U1") (pin "21") (pinfunction "VREG_1V2_21") (pintype "unspecified"))
    )
    (net (code "82") (name "unconnected-(U1-VREG_2V7-Pad23)") (class "Default")
      (node (ref "U1") (pin "23") (pinfunction "VREG_2V7_23") (pintype "unspecified"))
    )
    (net (code "83") (name "unconnected-(U1-VSYS-Pad22)") (class "Default")
      (node (ref "U1") (pin "22") (pinfunction "VSYS_22") (pintype "unspecified"))
    )
    (net (code "84") (name "unconnected-(U4-AIN2-Pad6)") (class "Default")
      (node (ref "U4") (pin "6") (pinfunction "AIN2_6") (pintype "unspecified"))
    )
    (net (code "85") (name "unconnected-(U4-AIN3-Pad7)") (class "Default")
      (node (ref "U4") (pin "7") (pinfunction "AIN3_7") (pintype "unspecified"))
    )
    (net (code "86") (name "unconnected-(U4-ALERT{slash}RDY-Pad2)") (class "Default")
      (node (ref "U4") (pin "2") (pinfunction "ALERT/RDY_2") (pintype "unspecified"))
    )
    (net (code "87") (name "unconnected-(U6-NC-Pad2)") (class "Default")
      (node (ref "U6") (pin "2") (pinfunction "NC_2") (pintype "unspecified"))
    )
    (net (code "88") (name "unconnected-(U6-NC-Pad3)") (class "Default")
      (node (ref "U6") (pin "3") (pinfunction "NC_3") (pintype "unspecified"))
    )
    (net (code "89") (name "unconnected-(U6-VOCM-Pad11)") (class "Default")
      (node (ref "U6") (pin "11") (pinfunction "VOCM_11") (pintype "unspecified"))
    )
    (net (code "90") (name "unconnected-(U13-FREQ-Pad6)") (class "Default")
      (node (ref "U13") (pin "6") (pinfunction "FREQ_6") (pintype "unspecified"))
    )
    (net (code "91") (name "unconnected-(U14-NC-Pad4)") (class "Default")
      (node (ref "U14") (pin "4") (pinfunction "NC_4") (pintype "unspecified"))
    )
    (net (code "92") (name "unconnected-(U15-IO14-Pad22)") (class "Default")
      (node (ref "U15") (pin "22") (pinfunction "IO14_22") (pintype "unspecified"))
    )
    (net (code "93") (name "unconnected-(U15-IO21-Pad23)") (class "Default")
      (node (ref "U15") (pin "23") (pinfunction "IO21_23") (pintype "unspecified"))
    )
    (net (code "94") (name "unconnected-(U15-IO35-Pad28)") (class "Default")
      (node (ref "U15") (pin "28") (pinfunction "IO35_28") (pintype "unspecified"))
    )
    (net (code "95") (name "unconnected-(U15-IO36-Pad29)") (class "Default")
      (node (ref "U15") (pin "29") (pinfunction "IO36_29") (pintype "unspecified"))
    )
    (net (code "96") (name "unconnected-(U15-IO37-Pad30)") (class "Default")
      (node (ref "U15") (pin "30") (pinfunction "IO37_30") (pintype "unspecified"))
    )
    (net (code "97") (name "unconnected-(U15-IO38-Pad31)") (class "Default")
      (node (ref "U15") (pin "31") (pinfunction "IO38_31") (pintype "unspecified"))
    )
    (net (code "98") (name "unconnected-(U15-IO42-Pad35)") (class "Default")
      (node (ref "U15") (pin "35") (pinfunction "IO42_35") (pintype "unspecified"))
    )
    (net (code "99") (name "unconnected-(U15-IO45-Pad26)") (class "Default")
      (node (ref "U15") (pin "26") (pinfunction "IO45_26") (pintype "unspecified"))
    )
    (net (code "100") (name "unconnected-(U15-IO46-Pad16)") (class "Default")
      (node (ref "U15") (pin "16") (pinfunction "IO46_16") (pintype "unspecified"))
    )
    (net (code "101") (name "unconnected-(U15-IO47-Pad24)") (class "Default")
      (node (ref "U15") (pin "24") (pinfunction "IO47_24") (pintype "unspecified"))
    )
    (net (code "102") (name "unconnected-(U15-IO48-Pad25)") (class "Default")
      (node (ref "U15") (pin "25") (pinfunction "IO48_25") (pintype "unspecified"))
    )
    (net (code "103") (name "unconnected-(U15-RXD0-Pad36)") (class "Default")
      (node (ref "U15") (pin "36") (pinfunction "RXD0_36") (pintype "unspecified"))
    )
    (net (code "104") (name "unconnected-(U15-TXD0-Pad37)") (class "Default")
      (node (ref "U15") (pin "37") (pinfunction "TXD0_37") (pintype "unspecified"))
    )
    (net (code "105") (name "unconnected-(USBC1-DN1-PadA7)") (class "Default")
      (node (ref "USBC1") (pin "A7") (pinfunction "DN1_A7") (pintype "unspecified"))
    )
    (net (code "106") (name "unconnected-(USBC1-DN2-PadB7)") (class "Default")
      (node (ref "USBC1") (pin "B7") (pinfunction "DN2_B7") (pintype "unspecified"))
    )
    (net (code "107") (name "unconnected-(USBC1-DP1-PadA6)") (class "Default")
      (node (ref "USBC1") (pin "A6") (pinfunction "DP1_A6") (pintype "unspecified"))
    )
    (net (code "108") (name "unconnected-(USBC1-DP2-PadB6)") (class "Default")
      (node (ref "USBC1") (pin "B6") (pinfunction "DP2_B6") (pintype "unspecified"))
    )
    (net (code "109") (name "unconnected-(USBC1-EH-Pad1)") (class "Default")
      (node (ref "USBC1") (pin "1") (pinfunction "EH_1") (pintype "unspecified"))
    )
    (net (code "110") (name "unconnected-(USBC1-EH-Pad2)") (class "Default")
      (node (ref "USBC1") (pin "2") (pinfunction "EH_2") (pintype "unspecified"))
    )
    (net (code "111") (name "unconnected-(USBC1-EH-Pad3)") (class "Default")
      (node (ref "USBC1") (pin "3") (pinfunction "EH_3") (pintype "unspecified"))
    )
    (net (code "112") (name "unconnected-(USBC1-EH-Pad4)") (class "Default")
      (node (ref "USBC1") (pin "4") (pinfunction "EH_4") (pintype "unspecified"))
    )
    (net (code "113") (name "unconnected-(USBC1-SBU1-PadA8)") (class "Default")
      (node (ref "USBC1") (pin "A8") (pinfunction "SBU1_A8") (pintype "unspecified"))
    )
    (net (code "114") (name "unconnected-(USBC1-SBU2-PadB8)") (class "Default")
      (node (ref "USBC1") (pin "B8") (pinfunction "SBU2_B8") (pintype "unspecified"))
    )
    (net (code "115") (name "unconnected-(USBC2-CC1-PadA5)") (class "Default")
      (node (ref "USBC2") (pin "A5") (pinfunction "CC1_A5") (pintype "unspecified"))
    )
    (net (code "116") (name "unconnected-(USBC2-CC2-PadB5)") (class "Default")
      (node (ref "USBC2") (pin "B5") (pinfunction "CC2_B5") (pintype "unspecified"))
    )
    (net (code "117") (name "unconnected-(USBC2-EH-Pad1)") (class "Default")
      (node (ref "USBC2") (pin "1") (pinfunction "EH_1") (pintype "unspecified"))
    )
    (net (code "118") (name "unconnected-(USBC2-EH-Pad2)") (class "Default")
      (node (ref "USBC2") (pin "2") (pinfunction "EH_2") (pintype "unspecified"))
    )
    (net (code "119") (name "unconnected-(USBC2-EH-Pad3)") (class "Default")
      (node (ref "USBC2") (pin "3") (pinfunction "EH_3") (pintype "unspecified"))
    )
    (net (code "120") (name "unconnected-(USBC2-EH-Pad4)") (class "Default")
      (node (ref "USBC2") (pin "4") (pinfunction "EH_4") (pintype "unspecified"))
    )
    (net (code "121") (name "unconnected-(USBC2-SBU1-PadA8)") (class "Default")
      (node (ref "USBC2") (pin "A8") (pinfunction "SBU1_A8") (pintype "unspecified"))
    )
    (net (code "122") (name "unconnected-(USBC2-SBU2-PadB8)") (class "Default")
      (node (ref "USBC2") (pin "B8") (pinfunction "SBU2_B8") (pintype "unspecified"))
    )
    (net (code "123") (name "unconnected-(USBC2-VBUS-PadB4A9)") (class "Default")
      (node (ref "USBC2") (pin "B4A9") (pinfunction "VBUS_B4A9") (pintype "unspecified"))
    )
    (net (code "124") (name "unconnected-(USBC3-CC1-PadA5)") (class "Default")
      (node (ref "USBC3") (pin "A5") (pinfunction "CC1_A5") (pintype "unspecified"))
    )
    (net (code "125") (name "unconnected-(USBC3-CC2-PadB5)") (class "Default")
      (node (ref "USBC3") (pin "B5") (pinfunction "CC2_B5") (pintype "unspecified"))
    )
    (net (code "126") (name "unconnected-(USBC3-EH-Pad1)") (class "Default")
      (node (ref "USBC3") (pin "1") (pinfunction "EH_1") (pintype "unspecified"))
    )
    (net (code "127") (name "unconnected-(USBC3-EH-Pad2)") (class "Default")
      (node (ref "USBC3") (pin "2") (pinfunction "EH_2") (pintype "unspecified"))
    )
    (net (code "128") (name "unconnected-(USBC3-EH-Pad3)") (class "Default")
      (node (ref "USBC3") (pin "3") (pinfunction "EH_3") (pintype "unspecified"))
    )
    (net (code "129") (name "unconnected-(USBC3-EH-Pad4)") (class "Default")
      (node (ref "USBC3") (pin "4") (pinfunction "EH_4") (pintype "unspecified"))
    )
    (net (code "130") (name "unconnected-(USBC3-SBU1-PadA8)") (class "Default")
      (node (ref "USBC3") (pin "A8") (pinfunction "SBU1_A8") (pintype "unspecified"))
    )
    (net (code "131") (name "unconnected-(USBC3-SBU2-PadB8)") (class "Default")
      (node (ref "USBC3") (pin "B8") (pinfunction "SBU2_B8") (pintype "unspecified"))
    )
    (net (code "132") (name "unconnected-(USBC3-VBUS-PadB4A9)") (class "Default")
      (node (ref "USBC3") (pin "B4A9") (pinfunction "VBUS_B4A9") (pintype "unspecified"))
    )
  )
)
